# 1A20J3_1A21J5_A.net
KiCad netlist of a schematic drawn in Altium Designer
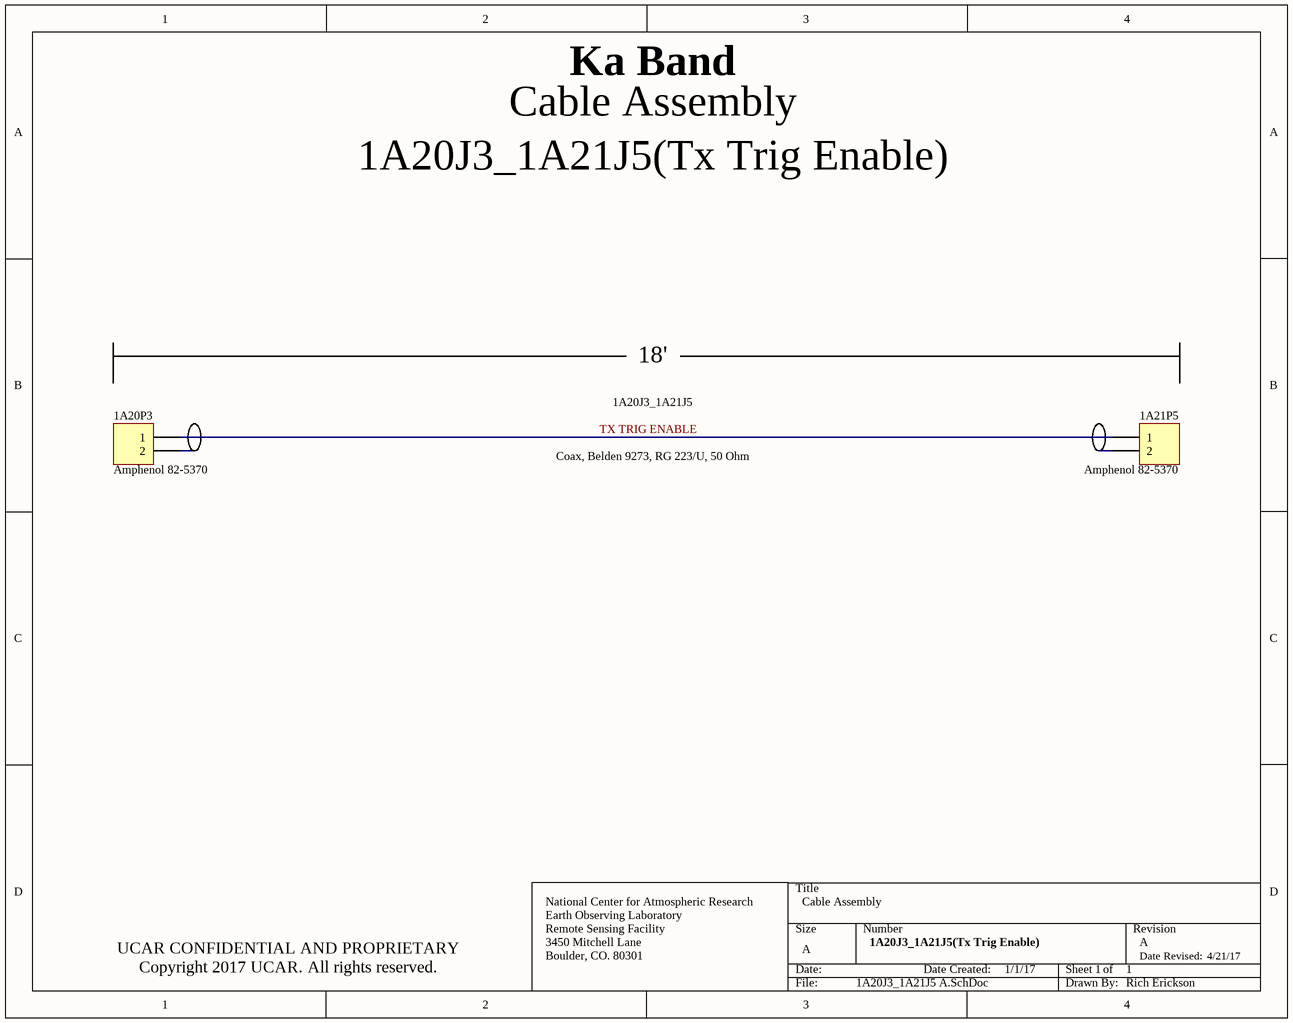
[diagram p0: 1A20J3_1A21J5 A.SchDoc]

(export (version "E")
  (design (tool "Eeschema 10.0.6"))
  (components
    (comp (ref "1A20P3")
      (value "Amphenol 82-5370")
      (footprint "HDR1X2")
      (description "Header, 2-Pin")
      (fields (field (name "PUBLISHER") "Altium Limited"))
      (libsource (lib "Miscellaneous Connectors") (part "Header 2"))
    )
    (comp (ref "1A21P5")
      (value "Amphenol 82-5370")
      (footprint "HDR1X2")
      (description "Header, 2-Pin")
      (fields (field (name "PUBLISHER") "Altium Limited"))
      (libsource (lib "") (part "Header 2_1"))
    )
  )
  (nets
    (net (code "1") (name "/TX TRIG ENABLE") (class "Default")
      (node (ref "1A20P3") (pin "1") (pinfunction "1_1") (pintype "passive"))
      (node (ref "1A21P5") (pin "1") (pinfunction "1_1") (pintype "passive"))
    )
    (net (code "2") (name "unconnected-(1A20P3-Pad2)") (class "Default")
      (node (ref "1A20P3") (pin "2") (pinfunction "2_2") (pintype "passive"))
    )
    (net (code "3") (name "unconnected-(1A21P5-Pad2)") (class "Default")
      (node (ref "1A21P5") (pin "2") (pinfunction "2_2") (pintype "passive"))
    )
  )
)
